# lit-bit.net
KiCad netlist of a schematic drawn in EAGLE
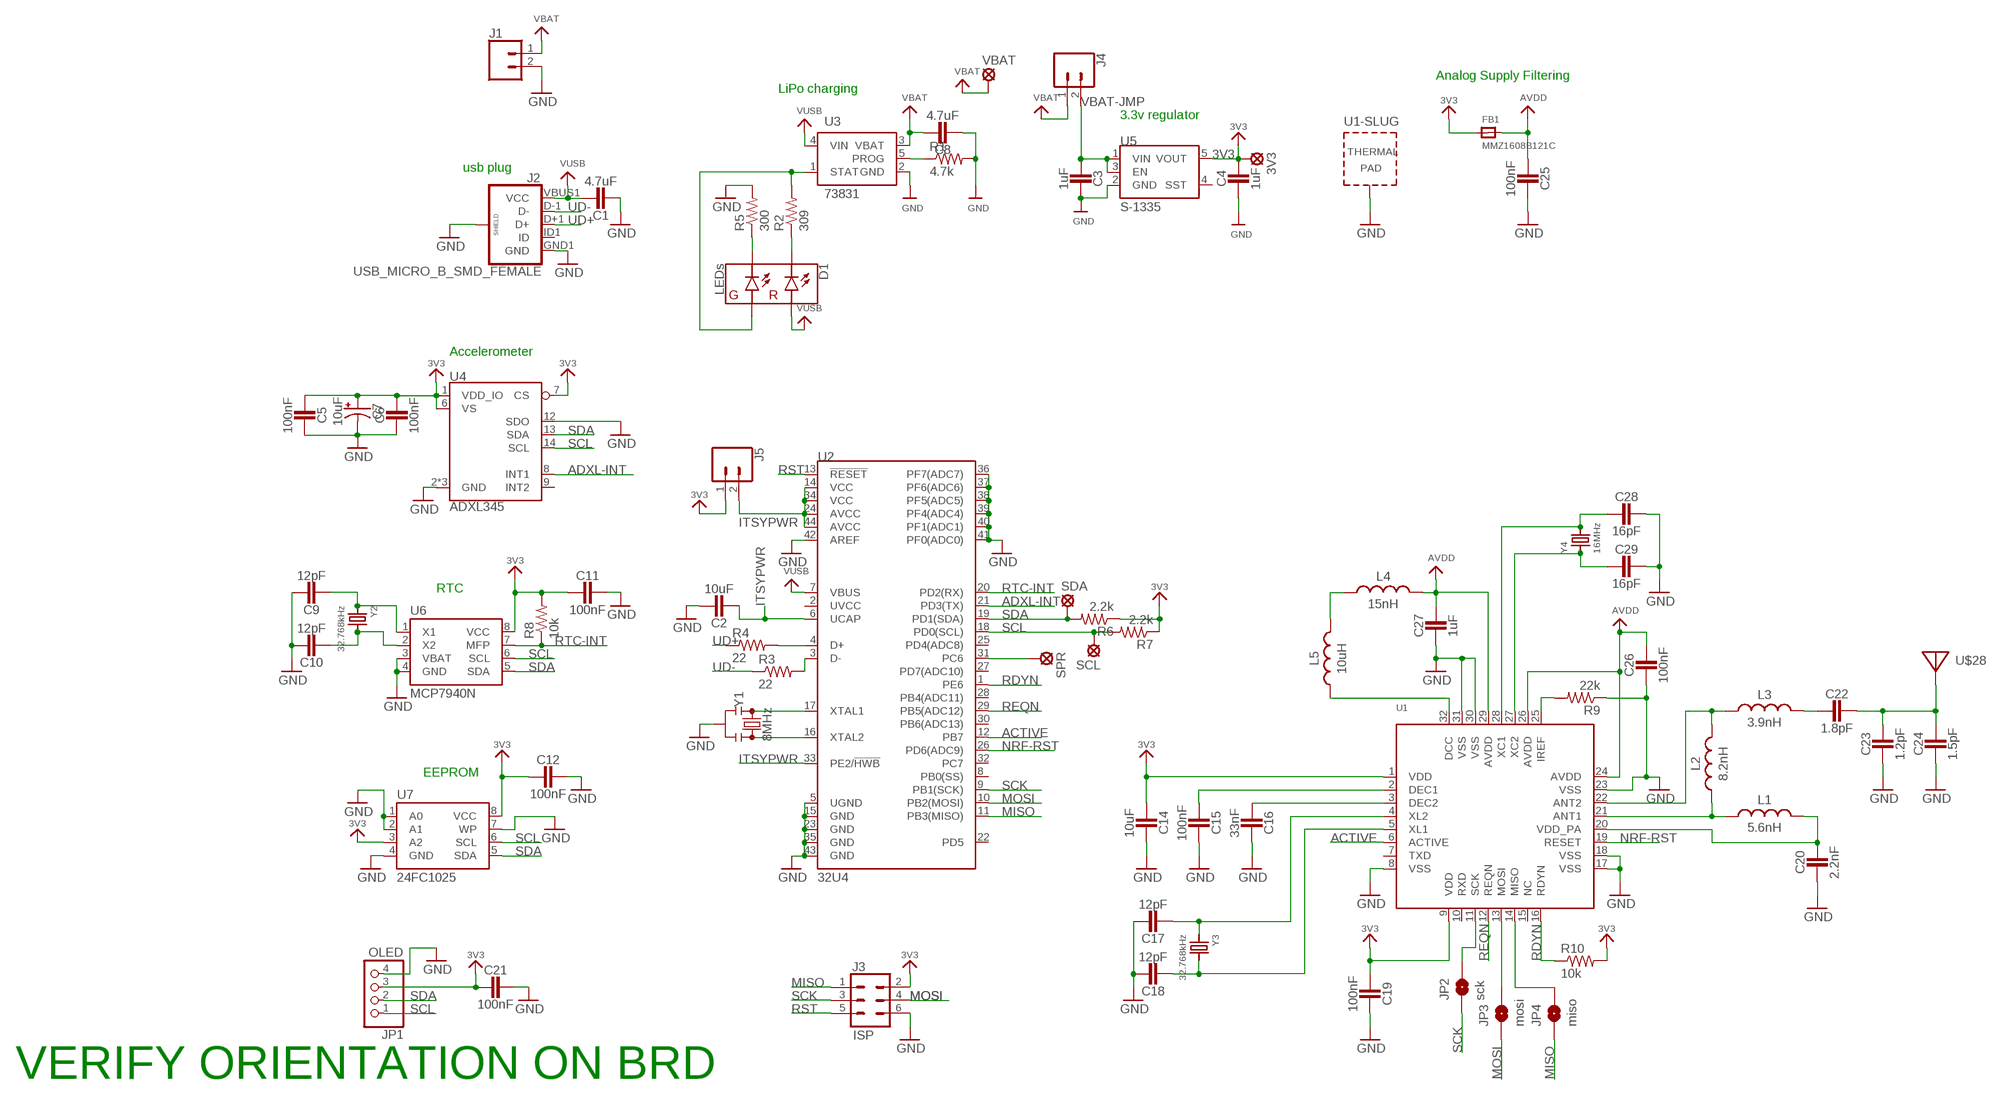
[diagram p0: schematic, sheet 1]

(export (version "E")
  (design (tool "Eeschema 10.0.6"))
  (components
    (comp (ref "3V3")
      (value "LSP10")
      (footprint "eagle-import:LSP10")
      (libsource (lib "eagle-import") (part "LSP10"))
    )
    (comp (ref "C1")
      (value "4.7uF")
      (footprint "eagle-import:0603")
      (libsource (lib "eagle-import") (part "CAP_NONPOL0603"))
    )
    (comp (ref "C2")
      (value "10uF")
      (footprint "eagle-import:0603")
      (libsource (lib "eagle-import") (part "CAP_NONPOL0603"))
    )
    (comp (ref "C3")
      (value "1uF")
      (footprint "eagle-import:0603")
      (libsource (lib "eagle-import") (part "CAP_NONPOL0603"))
    )
    (comp (ref "C4")
      (value "1uF")
      (footprint "eagle-import:0603")
      (libsource (lib "eagle-import") (part "CAP_NONPOL0603"))
    )
    (comp (ref "C5")
      (value "100nF")
      (footprint "eagle-import:0603")
      (libsource (lib "eagle-import") (part "CAP_NONPOL0603"))
    )
    (comp (ref "C6")
      (value "100nF")
      (footprint "eagle-import:0603")
      (libsource (lib "eagle-import") (part "CAP_NONPOL0603"))
    )
    (comp (ref "C7")
      (value "10uF")
      (footprint "eagle-import:0805-POLAR")
      (libsource (lib "eagle-import") (part "CAP_POL"))
    )
    (comp (ref "C8")
      (value "4.7uF")
      (footprint "eagle-import:0603")
      (libsource (lib "eagle-import") (part "CAP_NONPOL0603"))
    )
    (comp (ref "C9")
      (value "12pF")
      (footprint "eagle-import:0603")
      (libsource (lib "eagle-import") (part "CAP_NONPOL0603"))
    )
    (comp (ref "C10")
      (value "12pF")
      (footprint "eagle-import:0603")
      (libsource (lib "eagle-import") (part "CAP_NONPOL0603"))
    )
    (comp (ref "C11")
      (value "100nF")
      (footprint "eagle-import:0603")
      (libsource (lib "eagle-import") (part "CAP_NONPOL0603"))
    )
    (comp (ref "C12")
      (value "100nF")
      (footprint "eagle-import:0603")
      (libsource (lib "eagle-import") (part "CAP_NONPOL0603"))
    )
    (comp (ref "C14")
      (value "10uF")
      (footprint "eagle-import:0603")
      (libsource (lib "eagle-import") (part "CAP_NONPOL0603"))
    )
    (comp (ref "C15")
      (value "100nF")
      (footprint "eagle-import:0603")
      (libsource (lib "eagle-import") (part "CAP_NONPOL0603"))
    )
    (comp (ref "C16")
      (value "33nF")
      (footprint "eagle-import:0603")
      (libsource (lib "eagle-import") (part "CAP_NONPOL0603"))
    )
    (comp (ref "C17")
      (value "12pF")
      (footprint "eagle-import:0603")
      (libsource (lib "eagle-import") (part "CAP_NONPOL0603"))
    )
    (comp (ref "C18")
      (value "12pF")
      (footprint "eagle-import:0603")
      (libsource (lib "eagle-import") (part "CAP_NONPOL0603"))
    )
    (comp (ref "C19")
      (value "100nF")
      (footprint "eagle-import:0603")
      (libsource (lib "eagle-import") (part "CAP_NONPOL0603"))
    )
    (comp (ref "C20")
      (value "2.2nF")
      (footprint "eagle-import:0603")
      (libsource (lib "eagle-import") (part "CAP_NONPOL0603"))
    )
    (comp (ref "C21")
      (value "100nF")
      (footprint "eagle-import:0603")
      (libsource (lib "eagle-import") (part "CAP_NONPOL0603"))
    )
    (comp (ref "C22")
      (value "1.8pF")
      (footprint "eagle-import:0603")
      (libsource (lib "eagle-import") (part "CAP_NONPOL0603"))
    )
    (comp (ref "C23")
      (value "1.2pF")
      (footprint "eagle-import:0603")
      (libsource (lib "eagle-import") (part "CAP_NONPOL0603"))
    )
    (comp (ref "C24")
      (value "1.5pF")
      (footprint "eagle-import:0603")
      (libsource (lib "eagle-import") (part "CAP_NONPOL0603"))
    )
    (comp (ref "C25")
      (value "100nF")
      (footprint "eagle-import:0603")
      (libsource (lib "eagle-import") (part "CAP_NONPOL0603"))
    )
    (comp (ref "C26")
      (value "100nF")
      (footprint "eagle-import:0603")
      (libsource (lib "eagle-import") (part "CAP_NONPOL0603"))
    )
    (comp (ref "C27")
      (value "1uF")
      (footprint "eagle-import:0603")
      (libsource (lib "eagle-import") (part "CAP_NONPOL0603"))
    )
    (comp (ref "C28")
      (value "16pF")
      (footprint "eagle-import:0603")
      (libsource (lib "eagle-import") (part "CAP_NONPOL0603"))
    )
    (comp (ref "C29")
      (value "16pF")
      (footprint "eagle-import:0603")
      (libsource (lib "eagle-import") (part "CAP_NONPOL0603"))
    )
    (comp (ref "D1")
      (value "LEDs")
      (footprint "eagle-import:0606")
      (libsource (lib "eagle-import") (part "LED-RGSMIT"))
    )
    (comp (ref "FB1")
      (value "MMZ1608B121C")
      (footprint "eagle-import:0805")
      (libsource (lib "eagle-import") (part "FERRITE0805"))
    )
    (comp (ref "J1")
      (value "CONN_02-JST-2MM-SMT")
      (footprint "eagle-import:JST-2-SMD")
      (libsource (lib "eagle-import") (part "CONN_02-JST-2MM-SMT"))
    )
    (comp (ref "J2")
      (value "USB_MICRO_B_SMD_FEMALE")
      (footprint "eagle-import:USB-B-MICRO-SMD")
      (libsource (lib "eagle-import") (part "USB_MICRO_B_SMD_FEMALE"))
    )
    (comp (ref "J3")
      (value "ISP")
      (footprint "eagle-import:2X3")
      (libsource (lib "eagle-import") (part "CONN_03X22X3_SILK_MALE_PTH"))
    )
    (comp (ref "J4")
      (value "CONN_02")
      (footprint "eagle-import:1X02")
      (libsource (lib "eagle-import") (part "CONN_02"))
    )
    (comp (ref "J5")
      (value "CONN_02")
      (footprint "eagle-import:1X02")
      (libsource (lib "eagle-import") (part "CONN_02"))
    )
    (comp (ref "JP1")
      (value "OLED")
      (footprint "eagle-import:1X04_ROUND")
      (libsource (lib "eagle-import") (part "HEADER-1X4ROUND"))
    )
    (comp (ref "JP2")
      (value "sck")
      (footprint "eagle-import:SMT-JUMPER_2_NO_SILK")
      (libsource (lib "eagle-import") (part "JUMPER-SMT_2_NO_SILK"))
    )
    (comp (ref "JP3")
      (value "mosi")
      (footprint "eagle-import:SMT-JUMPER_2_NO_SILK")
      (libsource (lib "eagle-import") (part "JUMPER-SMT_2_NO_SILK"))
    )
    (comp (ref "JP4")
      (value "miso")
      (footprint "eagle-import:SMT-JUMPER_2_NO_SILK")
      (libsource (lib "eagle-import") (part "JUMPER-SMT_2_NO_SILK"))
    )
    (comp (ref "L1")
      (value "5.6nH")
      (footprint "eagle-import:0603")
      (libsource (lib "eagle-import") (part "INDUCTOR0603"))
    )
    (comp (ref "L2")
      (value "8.2nH")
      (footprint "eagle-import:0603")
      (libsource (lib "eagle-import") (part "INDUCTOR0603"))
    )
    (comp (ref "L3")
      (value "3.9nH")
      (footprint "eagle-import:0603")
      (libsource (lib "eagle-import") (part "INDUCTOR0603"))
    )
    (comp (ref "L4")
      (value "15nH")
      (footprint "eagle-import:0603")
      (libsource (lib "eagle-import") (part "INDUCTOR0603"))
    )
    (comp (ref "L5")
      (value "10uH")
      (footprint "eagle-import:0603")
      (libsource (lib "eagle-import") (part "INDUCTOR0603"))
    )
    (comp (ref "R1")
      (value "4.7k")
      (footprint "eagle-import:0603")
      (libsource (lib "eagle-import") (part "RES-0603"))
    )
    (comp (ref "R2")
      (value "309")
      (footprint "eagle-import:0603")
      (libsource (lib "eagle-import") (part "RES-0603"))
    )
    (comp (ref "R3")
      (value "22")
      (footprint "eagle-import:0603")
      (libsource (lib "eagle-import") (part "RES-0603"))
    )
    (comp (ref "R4")
      (value "22")
      (footprint "eagle-import:0603")
      (libsource (lib "eagle-import") (part "RES-0603"))
    )
    (comp (ref "R5")
      (value "300")
      (footprint "eagle-import:0603")
      (libsource (lib "eagle-import") (part "RES-0603"))
    )
    (comp (ref "R6")
      (value "2.2k")
      (footprint "eagle-import:0603")
      (libsource (lib "eagle-import") (part "RES-0603"))
    )
    (comp (ref "R7")
      (value "2.2k")
      (footprint "eagle-import:0603")
      (libsource (lib "eagle-import") (part "RES-0603"))
    )
    (comp (ref "R8")
      (value "10k")
      (footprint "eagle-import:0603")
      (libsource (lib "eagle-import") (part "RES-0603"))
    )
    (comp (ref "R9")
      (value "22k")
      (footprint "eagle-import:0603")
      (libsource (lib "eagle-import") (part "RES-0603"))
    )
    (comp (ref "R10")
      (value "10k")
      (footprint "eagle-import:0603")
      (libsource (lib "eagle-import") (part "RES-0603"))
    )
    (comp (ref "SCL")
      (value "LSP10")
      (footprint "eagle-import:LSP10")
      (libsource (lib "eagle-import") (part "LSP10"))
    )
    (comp (ref "SDA")
      (value "LSP10")
      (footprint "eagle-import:LSP10")
      (libsource (lib "eagle-import") (part "LSP10"))
    )
    (comp (ref "SPR")
      (value "LSP10")
      (footprint "eagle-import:LSP10")
      (libsource (lib "eagle-import") (part "LSP10"))
    )
    (comp (ref "U$28")
      (value "ANTENNA_PCBNRF8001_1.6MM")
      (footprint "eagle-import:ANT_PCB_2.4GHZ_NRF8001_1.6MM_1OZ")
      (libsource (lib "eagle-import") (part "ANTENNA_PCBNRF8001_1.6MM"))
    )
    (comp (ref "U1")
      (value "NRF8001")
      (footprint "eagle-import:QFN32_5MM")
      (libsource (lib "eagle-import") (part "NRF8001"))
    )
    (comp (ref "U2")
      (value "32U4")
      (footprint "eagle-import:TQFP44")
      (libsource (lib "eagle-import") (part "ATMEGA32U4TQFP-44"))
    )
    (comp (ref "U3")
      (value "73831")
      (footprint "eagle-import:SOT23-5")
      (libsource (lib "eagle-import") (part "MCP73831T"))
    )
    (comp (ref "U4")
      (value "ADXL345")
      (footprint "eagle-import:LGA-14")
      (libsource (lib "eagle-import") (part "ADXL345"))
    )
    (comp (ref "U5")
      (value "S-1335")
      (footprint "eagle-import:SOT23-5")
      (libsource (lib "eagle-import") (part "S-1335M33"))
    )
    (comp (ref "U6")
      (value "MCP7940N")
      (footprint "eagle-import:8-SOIC_HAND_SOLDER")
      (libsource (lib "eagle-import") (part "MCP7940N"))
    )
    (comp (ref "U7")
      (value "24FC1025")
      (footprint "eagle-import:8-SOIC_HAND_SOLDER")
      (libsource (lib "eagle-import") (part "24FC1025"))
    )
    (comp (ref "VBAT")
      (value "LSP10")
      (footprint "eagle-import:LSP10")
      (libsource (lib "eagle-import") (part "LSP10"))
    )
    (comp (ref "Y1")
      (value "8MHz")
      (footprint "eagle-import:RESONATOR-SMD-3.2X1.3")
      (libsource (lib "eagle-import") (part "RESONATOR-8MHZSMD_3.2X1.3"))
    )
    (comp (ref "Y2")
      (value "32.768kHz")
      (footprint "eagle-import:CRYSTAL_8X3.8")
      (libsource (lib "eagle-import") (part "CRYSTAL8X3.8SMT"))
    )
    (comp (ref "Y3")
      (value "32.768kHz")
      (footprint "eagle-import:CRYSTAL_8X3.8")
      (libsource (lib "eagle-import") (part "CRYSTAL8X3.8SMT"))
    )
    (comp (ref "Y4")
      (value "16MHz")
      (footprint "eagle-import:CRYSTAL_3.2X2.5")
      (libsource (lib "eagle-import") (part "CRYSTALTHIN"))
    )
  )
  (nets
    (net (code "1") (name "/ACTIVE") (class "Default")
      (node (ref "U1") (pin "6") (pinfunction "ACTIVE_6") (pintype "output"))
      (node (ref "U2") (pin "12") (pinfunction "PB7_12") (pintype "bidirectional"))
    )
    (net (code "2") (name "/ADXL-INT") (class "Default")
      (node (ref "U2") (pin "21") (pinfunction "PD3(TX)_21") (pintype "bidirectional"))
      (node (ref "U4") (pin "8") (pinfunction "INT1_8") (pintype "output"))
    )
    (net (code "3") (name "/ITSYPWR") (class "Default")
      (node (ref "C2") (pin "2") (pinfunction "2_2") (pintype "passive"))
      (node (ref "J5") (pin "2") (pinfunction "2_2") (pintype "passive"))
      (node (ref "U2") (pin "14") (pinfunction "VCC_14") (pintype "bidirectional"))
      (node (ref "U2") (pin "24") (pinfunction "AVCC_24") (pintype "bidirectional"))
      (node (ref "U2") (pin "33") (pinfunction "PE2/~{HWB}_33") (pintype "bidirectional"))
      (node (ref "U2") (pin "34") (pinfunction "VCC_34") (pintype "bidirectional"))
      (node (ref "U2") (pin "44") (pinfunction "AVCC_44") (pintype "bidirectional"))
      (node (ref "U2") (pin "6") (pinfunction "UCAP_6") (pintype "bidirectional"))
    )
    (net (code "4") (name "/MISO") (class "Default")
      (node (ref "J3") (pin "1") (pinfunction "1_1") (pintype "bidirectional"))
      (node (ref "JP4") (pin "1") (pinfunction "1_1") (pintype "passive"))
      (node (ref "U2") (pin "11") (pinfunction "PB3(MISO)_11") (pintype "bidirectional"))
    )
    (net (code "5") (name "/MOSI") (class "Default")
      (node (ref "J3") (pin "4") (pinfunction "4_4") (pintype "bidirectional"))
      (node (ref "JP3") (pin "1") (pinfunction "1_1") (pintype "passive"))
      (node (ref "U2") (pin "10") (pinfunction "PB2(MOSI)_10") (pintype "bidirectional"))
    )
    (net (code "6") (name "/NRF-RST") (class "Default")
      (node (ref "U1") (pin "19") (pinfunction "RESET_19") (pintype "input"))
      (node (ref "U2") (pin "26") (pinfunction "PD6(ADC9)_26") (pintype "bidirectional"))
    )
    (net (code "7") (name "/RDYN") (class "Default")
      (node (ref "R10") (pin "1") (pinfunction "1_1") (pintype "passive"))
      (node (ref "U1") (pin "16") (pinfunction "RDYN_16") (pintype "output"))
      (node (ref "U2") (pin "1") (pinfunction "PE6_1") (pintype "bidirectional"))
    )
    (net (code "8") (name "/REQN") (class "Default")
      (node (ref "U1") (pin "12") (pinfunction "REQN_12") (pintype "input"))
      (node (ref "U2") (pin "29") (pinfunction "PB5(ADC12)_29") (pintype "bidirectional"))
    )
    (net (code "9") (name "/RST") (class "Default")
      (node (ref "J3") (pin "5") (pinfunction "5_5") (pintype "bidirectional"))
      (node (ref "U2") (pin "13") (pinfunction "~{RESET}_13") (pintype "bidirectional"))
    )
    (net (code "10") (name "/RTC-INT") (class "Default")
      (node (ref "R8") (pin "1") (pinfunction "1_1") (pintype "passive"))
      (node (ref "U2") (pin "20") (pinfunction "PD2(RX)_20") (pintype "bidirectional"))
      (node (ref "U6") (pin "7") (pinfunction "MFP_7") (pintype "output"))
    )
    (net (code "11") (name "/SCK") (class "Default")
      (node (ref "J3") (pin "3") (pinfunction "3_3") (pintype "bidirectional"))
      (node (ref "JP2") (pin "1") (pinfunction "1_1") (pintype "passive"))
      (node (ref "U2") (pin "9") (pinfunction "PB1(SCK)_9") (pintype "bidirectional"))
    )
    (net (code "12") (name "/SCL") (class "Default")
      (node (ref "JP1") (pin "1") (pinfunction "1_1") (pintype "passive"))
      (node (ref "R7") (pin "2") (pinfunction "2_2") (pintype "passive"))
      (node (ref "SCL") (pin "MP") (pinfunction "MP_MP") (pintype "passive"))
      (node (ref "U2") (pin "18") (pinfunction "PD0(SCL)_18") (pintype "bidirectional"))
      (node (ref "U4") (pin "14") (pinfunction "SCL_14") (pintype "bidirectional"))
      (node (ref "U6") (pin "6") (pinfunction "SCL_6") (pintype "bidirectional"))
      (node (ref "U7") (pin "6") (pinfunction "SCL_6") (pintype "bidirectional"))
    )
    (net (code "13") (name "/SDA") (class "Default")
      (node (ref "JP1") (pin "2") (pinfunction "2_2") (pintype "passive"))
      (node (ref "R6") (pin "2") (pinfunction "2_2") (pintype "passive"))
      (node (ref "SDA") (pin "MP") (pinfunction "MP_MP") (pintype "passive"))
      (node (ref "U2") (pin "19") (pinfunction "PD1(SDA)_19") (pintype "bidirectional"))
      (node (ref "U4") (pin "13") (pinfunction "SDA_13") (pintype "bidirectional"))
      (node (ref "U6") (pin "5") (pinfunction "SDA_5") (pintype "bidirectional"))
      (node (ref "U7") (pin "5") (pinfunction "SDA_5") (pintype "bidirectional"))
    )
    (net (code "14") (name "/UD+") (class "Default")
      (node (ref "J2") (pin "D+1") (pinfunction "D+_D+1") (pintype "bidirectional"))
      (node (ref "R4") (pin "1") (pinfunction "1_1") (pintype "passive"))
    )
    (net (code "15") (name "/UD-") (class "Default")
      (node (ref "J2") (pin "D-1") (pinfunction "D-_D-1") (pintype "bidirectional"))
      (node (ref "R3") (pin "1") (pinfunction "1_1") (pintype "passive"))
    )
    (net (code "16") (name "/VBAT-JMP") (class "Default")
      (node (ref "C3") (pin "2") (pinfunction "2_2") (pintype "passive"))
      (node (ref "J4") (pin "2") (pinfunction "2_2") (pintype "passive"))
      (node (ref "U5") (pin "1") (pinfunction "VIN_1") (pintype "passive"))
      (node (ref "U5") (pin "3") (pinfunction "EN_3") (pintype "bidirectional"))
    )
    (net (code "17") (name "3V3") (class "Default")
      (node (ref "3V3") (pin "MP") (pinfunction "MP_MP") (pintype "passive"))
      (node (ref "C11") (pin "2") (pinfunction "2_2") (pintype "passive"))
      (node (ref "C12") (pin "2") (pinfunction "2_2") (pintype "passive"))
      (node (ref "C14") (pin "2") (pinfunction "2_2") (pintype "passive"))
      (node (ref "C19") (pin "2") (pinfunction "2_2") (pintype "passive"))
      (node (ref "C21") (pin "2") (pinfunction "2_2") (pintype "passive"))
      (node (ref "C4") (pin "1") (pinfunction "1_1") (pintype "passive"))
      (node (ref "C5") (pin "2") (pinfunction "2_2") (pintype "passive"))
      (node (ref "C6") (pin "1") (pinfunction "1_1") (pintype "passive"))
      (node (ref "C7") (pin "1") (pinfunction "+_1") (pintype "passive"))
      (node (ref "FB1") (pin "1") (pinfunction "P$1_1") (pintype "passive"))
      (node (ref "J3") (pin "2") (pinfunction "2_2") (pintype "bidirectional"))
      (node (ref "J5") (pin "1") (pinfunction "1_1") (pintype "passive"))
      (node (ref "JP1") (pin "3") (pinfunction "3_3") (pintype "passive"))
      (node (ref "R10") (pin "2") (pinfunction "2_2") (pintype "passive"))
      (node (ref "R6") (pin "1") (pinfunction "1_1") (pintype "passive"))
      (node (ref "R7") (pin "1") (pinfunction "1_1") (pintype "passive"))
      (node (ref "R8") (pin "2") (pinfunction "2_2") (pintype "passive"))
      (node (ref "U1") (pin "1") (pinfunction "VDD_1") (pintype "power_in"))
      (node (ref "U1") (pin "9") (pinfunction "VDD_9") (pintype "power_in"))
      (node (ref "U4") (pin "1") (pinfunction "VDD_IO_1") (pintype "passive"))
      (node (ref "U4") (pin "6") (pinfunction "VS_6") (pintype "passive"))
      (node (ref "U4") (pin "7") (pinfunction "CS_7") (pintype "bidirectional"))
      (node (ref "U5") (pin "5") (pinfunction "VOUT_5") (pintype "passive"))
      (node (ref "U6") (pin "8") (pinfunction "VCC_8") (pintype "passive"))
      (node (ref "U7") (pin "3") (pinfunction "A2_3") (pintype "bidirectional"))
      (node (ref "U7") (pin "8") (pinfunction "VCC_8") (pintype "power_in"))
    )
    (net (code "18") (name "AVDD") (class "Default")
      (node (ref "C25") (pin "2") (pinfunction "2_2") (pintype "passive"))
      (node (ref "C26") (pin "1") (pinfunction "1_1") (pintype "passive"))
      (node (ref "C27") (pin "1") (pinfunction "1_1") (pintype "passive"))
      (node (ref "FB1") (pin "2") (pinfunction "P$2_2") (pintype "passive"))
      (node (ref "L4") (pin "2") (pinfunction "2_2") (pintype "passive"))
      (node (ref "U1") (pin "24") (pinfunction "AVDD_24") (pintype "power_in"))
      (node (ref "U1") (pin "26") (pinfunction "AVDD_26") (pintype "power_in"))
      (node (ref "U1") (pin "29") (pinfunction "AVDD_29") (pintype "power_in"))
    )
    (net (code "19") (name "GND") (class "Default")
      (node (ref "C1") (pin "2") (pinfunction "2_2") (pintype "passive"))
      (node (ref "C10") (pin "1") (pinfunction "1_1") (pintype "passive"))
      (node (ref "C11") (pin "1") (pinfunction "1_1") (pintype "passive"))
      (node (ref "C12") (pin "1") (pinfunction "1_1") (pintype "passive"))
      (node (ref "C14") (pin "1") (pinfunction "1_1") (pintype "passive"))
      (node (ref "C15") (pin "1") (pinfunction "1_1") (pintype "passive"))
      (node (ref "C16") (pin "1") (pinfunction "1_1") (pintype "passive"))
      (node (ref "C17") (pin "1") (pinfunction "1_1") (pintype "passive"))
      (node (ref "C18") (pin "1") (pinfunction "1_1") (pintype "passive"))
      (node (ref "C19") (pin "1") (pinfunction "1_1") (pintype "passive"))
      (node (ref "C2") (pin "1") (pinfunction "1_1") (pintype "passive"))
      (node (ref "C20") (pin "2") (pinfunction "2_2") (pintype "passive"))
      (node (ref "C21") (pin "1") (pinfunction "1_1") (pintype "passive"))
      (node (ref "C23") (pin "2") (pinfunction "2_2") (pintype "passive"))
      (node (ref "C24") (pin "2") (pinfunction "2_2") (pintype "passive"))
      (node (ref "C25") (pin "1") (pinfunction "1_1") (pintype "passive"))
      (node (ref "C26") (pin "2") (pinfunction "2_2") (pintype "passive"))
      (node (ref "C27") (pin "2") (pinfunction "2_2") (pintype "passive"))
      (node (ref "C28") (pin "1") (pinfunction "1_1") (pintype "passive"))
      (node (ref "C29") (pin "1") (pinfunction "1_1") (pintype "passive"))
      (node (ref "C3") (pin "1") (pinfunction "1_1") (pintype "passive"))
      (node (ref "C4") (pin "2") (pinfunction "2_2") (pintype "passive"))
      (node (ref "C5") (pin "1") (pinfunction "1_1") (pintype "passive"))
      (node (ref "C6") (pin "2") (pinfunction "2_2") (pintype "passive"))
      (node (ref "C7") (pin "2") (pinfunction "-_2") (pintype "passive"))
      (node (ref "C8") (pin "2") (pinfunction "2_2") (pintype "passive"))
      (node (ref "C9") (pin "1") (pinfunction "1_1") (pintype "passive"))
      (node (ref "J1") (pin "2") (pinfunction "1_2") (pintype "passive"))
      (node (ref "J2") (pin "GND1") (pinfunction "GND_GND1") (pintype "passive"))
      (node (ref "J2") (pin "P$1") (pinfunction "SHIELD_P$1") (pintype "passive"))
      (node (ref "J2") (pin "P$3") (pinfunction "SHIELD_P$3") (pintype "passive"))
      (node (ref "J2") (pin "P$4") (pinfunction "SHIELD_P$4") (pintype "passive"))
      (node (ref "J2") (pin "P$5") (pinfunction "SHIELD_P$5") (pintype "passive"))
      (node (ref "J3") (pin "6") (pinfunction "6_6") (pintype "bidirectional"))
      (node (ref "JP1") (pin "4") (pinfunction "4_4") (pintype "passive"))
      (node (ref "R1") (pin "2") (pinfunction "2_2") (pintype "passive"))
      (node (ref "R5") (pin "2") (pinfunction "2_2") (pintype "passive"))
      (node (ref "R9") (pin "1") (pinfunction "1_1") (pintype "passive"))
      (node (ref "U1") (pin "17") (pinfunction "VSS_17") (pintype "power_in"))
      (node (ref "U1") (pin "18") (pinfunction "VSS_18") (pintype "power_in"))
      (node (ref "U1") (pin "23") (pinfunction "VSS_23") (pintype "power_in"))
      (node (ref "U1") (pin "30") (pinfunction "VSS_30") (pintype "power_in"))
      (node (ref "U1") (pin "31") (pinfunction "VSS_31") (pintype "power_in"))
      (node (ref "U1") (pin "33") (pinfunction "TP_33") (pintype "power_in"))
      (node (ref "U1") (pin "8") (pinfunction "VSS_8") (pintype "power_in"))
      (node (ref "U2") (pin "15") (pinfunction "GND_15") (pintype "bidirectional"))
      (node (ref "U2") (pin "23") (pinfunction "GND_23") (pintype "bidirectional"))
      (node (ref "U2") (pin "35") (pinfunction "GND_35") (pintype "bidirectional"))
      (node (ref "U2") (pin "36") (pinfunction "PF7(ADC7)_36") (pintype "bidirectional"))
      (node (ref "U2") (pin "37") (pinfunction "PF6(ADC6)_37") (pintype "bidirectional"))
      (node (ref "U2") (pin "38") (pinfunction "PF5(ADC5)_38") (pintype "bidirectional"))
      (node (ref "U2") (pin "39") (pinfunction "PF4(ADC4)_39") (pintype "bidirectional"))
      (node (ref "U2") (pin "40") (pinfunction "PF1(ADC1)_40") (pintype "bidirectional"))
      (node (ref "U2") (pin "41") (pinfunction "PF0(ADC0)_41") (pintype "bidirectional"))
      (node (ref "U2") (pin "42") (pinfunction "AREF_42") (pintype "bidirectional"))
      (node (ref "U2") (pin "43") (pinfunction "GND_43") (pintype "bidirectional"))
      (node (ref "U2") (pin "5") (pinfunction "UGND_5") (pintype "bidirectional"))
      (node (ref "U3") (pin "2") (pinfunction "GND_2") (pintype "passive"))
      (node (ref "U4") (pin "12") (pinfunction "SDO_12") (pintype "bidirectional"))
      (node (ref "U4") (pin "2") (pinfunction "GND_2") (pintype "passive"))
      (node (ref "U4") (pin "4") (pinfunction "GND_4") (pintype "passive"))
      (node (ref "U4") (pin "5") (pinfunction "GND_5") (pintype "passive"))
      (node (ref "U5") (pin "2") (pinfunction "GND_2") (pintype "passive"))
      (node (ref "U6") (pin "3") (pinfunction "VBAT_3") (pintype "passive"))
      (node (ref "U6") (pin "4") (pinfunction "GND_4") (pintype "passive"))
      (node (ref "U7") (pin "1") (pinfunction "A0_1") (pintype "bidirectional"))
      (node (ref "U7") (pin "2") (pinfunction "A1_2") (pintype "bidirectional"))
      (node (ref "U7") (pin "4") (pinfunction "GND_4") (pintype "power_in"))
      (node (ref "U7") (pin "7") (pinfunction "WP_7") (pintype "bidirectional"))
      (node (ref "Y1") (pin "2") (pinfunction "2_2") (pintype "passive"))
    )
    (net (code "20") (name "Net-(C22-Pad2)") (class "Default")
      (node (ref "C22") (pin "2") (pinfunction "2_2") (pintype "passive"))
      (node (ref "L3") (pin "2") (pinfunction "2_2") (pintype "passive"))
    )
    (net (code "21") (name "Net-(D1-GA)") (class "Default")
      (node (ref "D1") (pin "P$3") (pinfunction "GA_P$3") (pintype "passive"))
      (node (ref "R2") (pin "2") (pinfunction "2_2") (pintype "passive"))
      (node (ref "U3") (pin "1") (pinfunction "STAT_1") (pintype "bidirectional"))
    )
    (net (code "22") (name "Net-(D1-GC)") (class "Default")
      (node (ref "D1") (pin "P$4") (pinfunction "GC_P$4") (pintype "passive"))
      (node (ref "R5") (pin "1") (pinfunction "1_1") (pintype "passive"))
    )
    (net (code "23") (name "Net-(D1-RC)") (class "Default")
      (node (ref "D1") (pin "P$2") (pinfunction "RC_P$2") (pintype "passive"))
      (node (ref "R2") (pin "1") (pinfunction "1_1") (pintype "passive"))
    )
    (net (code "24") (name "Net-(L4-Pad1)") (class "Default")
      (node (ref "L4") (pin "1") (pinfunction "1_1") (pintype "passive"))
      (node (ref "L5") (pin "2") (pinfunction "2_2") (pintype "passive"))
    )
    (net (code "25") (name "Net-(U$28-P$1)") (class "Default")
      (node (ref "C22") (pin "1") (pinfunction "1_1") (pintype "passive"))
      (node (ref "C23") (pin "1") (pinfunction "1_1") (pintype "passive"))
      (node (ref "C24") (pin "1") (pinfunction "1_1") (pintype "passive"))
      (node (ref "U$28") (pin "FEED") (pinfunction "P$1_FEED") (pintype "passive"))
    )
    (net (code "26") (name "Net-(U1B-ANT1)") (class "Default")
      (node (ref "L1") (pin "1") (pinfunction "1_1") (pintype "passive"))
      (node (ref "L2") (pin "1") (pinfunction "1_1") (pintype "passive"))
      (node (ref "U1") (pin "21") (pinfunction "ANT1_21") (pintype "bidirectional"))
    )
    (net (code "27") (name "Net-(U1B-ANT2)") (class "Default")
      (node (ref "L2") (pin "2") (pinfunction "2_2") (pintype "passive"))
      (node (ref "L3") (pin "1") (pinfunction "1_1") (pintype "passive"))
      (node (ref "U1") (pin "22") (pinfunction "ANT2_22") (pintype "bidirectional"))
    )
    (net (code "28") (name "Net-(U1B-DCC)") (class "Default")
      (node (ref "L5") (pin "1") (pinfunction "1_1") (pintype "passive"))
      (node (ref "U1") (pin "32") (pinfunction "DCC_32") (pintype "bidirectional"))
    )
    (net (code "29") (name "Net-(U1B-DEC1)") (class "Default")
      (node (ref "C15") (pin "2") (pinfunction "2_2") (pintype "passive"))
      (node (ref "U1") (pin "2") (pinfunction "DEC1_2") (pintype "bidirectional"))
    )
    (net (code "30") (name "Net-(U1B-DEC2)") (class "Default")
      (node (ref "C16") (pin "2") (pinfunction "2_2") (pintype "passive"))
      (node (ref "U1") (pin "3") (pinfunction "DEC2_3") (pintype "bidirectional"))
    )
    (net (code "31") (name "Net-(U1B-IREF)") (class "Default")
      (node (ref "R9") (pin "2") (pinfunction "2_2") (pintype "passive"))
      (node (ref "U1") (pin "25") (pinfunction "IREF_25") (pintype "output"))
    )
    (net (code "32") (name "Net-(U1B-MISO)") (class "Default")
      (node (ref "JP4") (pin "2") (pinfunction "2_2") (pintype "passive"))
      (node (ref "U1") (pin "14") (pinfunction "MISO_14") (pintype "output"))
    )
    (net (code "33") (name "Net-(U1B-MOSI)") (class "Default")
      (node (ref "JP3") (pin "2") (pinfunction "2_2") (pintype "passive"))
      (node (ref "U1") (pin "13") (pinfunction "MOSI_13") (pintype "input"))
    )
    (net (code "34") (name "Net-(U1B-SCK)") (class "Default")
      (node (ref "JP2") (pin "2") (pinfunction "2_2") (pintype "passive"))
      (node (ref "U1") (pin "11") (pinfunction "SCK_11") (pintype "input"))
    )
    (net (code "35") (name "Net-(U1B-VDD_PA)") (class "Default")
      (node (ref "C20") (pin "1") (pinfunction "1_1") (pintype "passive"))
      (node (ref "L1") (pin "2") (pinfunction "2_2") (pintype "passive"))
      (node (ref "U1") (pin "20") (pinfunction "VDD_PA_20") (pintype "bidirectional"))
    )
    (net (code "36") (name "Net-(U1B-XC1)") (class "Default")
      (node (ref "C28") (pin "2") (pinfunction "2_2") (pintype "passive"))
      (node (ref "U1") (pin "28") (pinfunction "XC1_28") (pintype "input"))
      (node (ref "Y4") (pin "2") (pinfunction "2_2") (pintype "passive"))
    )
    (net (code "37") (name "Net-(U1B-XC2)") (class "Default")
      (node (ref "C29") (pin "2") (pinfunction "2_2") (pintype "passive"))
      (node (ref "U1") (pin "27") (pinfunction "XC2_27") (pintype "output"))
      (node (ref "Y4") (pin "1") (pinfunction "1_1") (pintype "passive"))
    )
    (net (code "38") (name "Net-(U1B-XL1)") (class "Default")
      (node (ref "C18") (pin "2") (pinfunction "2_2") (pintype "passive"))
      (node (ref "U1") (pin "5") (pinfunction "XL1_5") (pintype "input"))
      (node (ref "Y3") (pin "P$4") (pinfunction "2_P$4") (pintype "passive"))
    )
    (net (code "39") (name "Net-(U1B-XL2)") (class "Default")
      (node (ref "C17") (pin "2") (pinfunction "2_2") (pintype "passive"))
      (node (ref "U1") (pin "4") (pinfunction "XL2_4") (pintype "output"))
      (node (ref "Y3") (pin "P$1") (pinfunction "1_P$1") (pintype "passive"))
    )
    (net (code "40") (name "Net-(U2-D+)") (class "Default")
      (node (ref "R4") (pin "2") (pinfunction "2_2") (pintype "passive"))
      (node (ref "U2") (pin "4") (pinfunction "D+_4") (pintype "bidirectional"))
    )
    (net (code "41") (name "Net-(U2-D-)") (class "Default")
      (node (ref "R3") (pin "2") (pinfunction "2_2") (pintype "passive"))
      (node (ref "U2") (pin "3") (pinfunction "D-_3") (pintype "bidirectional"))
    )
    (net (code "42") (name "Net-(U2-PC6)") (class "Default")
      (node (ref "SPR") (pin "MP") (pinfunction "MP_MP") (pintype "passive"))
      (node (ref "U2") (pin "31") (pinfunction "PC6_31") (pintype "bidirectional"))
    )
    (net (code "43") (name "Net-(U2-XTAL1)") (class "Default")
      (node (ref "U2") (pin "17") (pinfunction "XTAL1_17") (pintype "bidirectional"))
      (node (ref "Y1") (pin "1") (pinfunction "1_1") (pintype "passive"))
    )
    (net (code "44") (name "Net-(U2-XTAL2)") (class "Default")
      (node (ref "U2") (pin "16") (pinfunction "XTAL2_16") (pintype "bidirectional"))
      (node (ref "Y1") (pin "3") (pinfunction "3_3") (pintype "passive"))
    )
    (net (code "45") (name "Net-(U3-PROG)") (class "Default")
      (node (ref "R1") (pin "1") (pinfunction "1_1") (pintype "passive"))
      (node (ref "U3") (pin "5") (pinfunction "PROG_5") (pintype "bidirectional"))
    )
    (net (code "46") (name "Net-(U6-X1)") (class "Default")
      (node (ref "C9") (pin "2") (pinfunction "2_2") (pintype "passive"))
      (node (ref "U6") (pin "1") (pinfunction "X1_1") (pintype "bidirectional"))
      (node (ref "Y2") (pin "P$1") (pinfunction "1_P$1") (pintype "passive"))
    )
    (net (code "47") (name "Net-(U6-X2)") (class "Default")
      (node (ref "C10") (pin "2") (pinfunction "2_2") (pintype "passive"))
      (node (ref "U6") (pin "2") (pinfunction "X2_2") (pintype "bidirectional"))
      (node (ref "Y2") (pin "P$4") (pinfunction "2_P$4") (pintype "passive"))
    )
    (net (code "48") (name "VBAT") (class "Default")
      (node (ref "C8") (pin "1") (pinfunction "1_1") (pintype "passive"))
      (node (ref "J1") (pin "1") (pinfunction "2_1") (pintype "passive"))
      (node (ref "J4") (pin "1") (pinfunction "1_1") (pintype "passive"))
      (node (ref "U3") (pin "3") (pinfunction "VBAT_3") (pintype "passive"))
      (node (ref "VBAT") (pin "MP") (pinfunction "MP_MP") (pintype "passive"))
    )
    (net (code "49") (name "VUSB") (class "Default")
      (node (ref "C1") (pin "1") (pinfunction "1_1") (pintype "passive"))
      (node (ref "D1") (pin "P$1") (pinfunction "RA_P$1") (pintype "passive"))
      (node (ref "J2") (pin "VBUS1") (pinfunction "VCC_VBUS1") (pintype "passive"))
      (node (ref "U2") (pin "7") (pinfunction "VBUS_7") (pintype "bidirectional"))
      (node (ref "U3") (pin "4") (pinfunction "VIN_4") (pintype "bidirectional"))
    )
    (net (code "50") (name "unconnected-(J2-ID-PadID1)") (class "Default")
      (node (ref "J2") (pin "ID1") (pinfunction "ID_ID1") (pintype "bidirectional"))
    )
    (net (code "51") (name "unconnected-(U1B-NC-Pad15)") (class "Default")
      (node (ref "U1") (pin "15") (pinfunction "NC_15") (pintype "no_connect"))
    )
    (net (code "52") (name "unconnected-(U1B-RXD-Pad10)") (class "Default")
      (node (ref "U1") (pin "10") (pinfunction "RXD_10") (pintype "input"))
    )
    (net (code "53") (name "unconnected-(U1B-TXD-Pad7)") (class "Default")
      (node (ref "U1") (pin "7") (pinfunction "TXD_7") (pintype "output"))
    )
    (net (code "54") (name "unconnected-(U2-PB0(SS)-Pad8)") (class "Default")
      (node (ref "U2") (pin "8") (pinfunction "PB0(SS)_8") (pintype "bidirectional"))
    )
    (net (code "55") (name "unconnected-(U2-PB4(ADC11)-Pad28)") (class "Default")
      (node (ref "U2") (pin "28") (pinfunction "PB4(ADC11)_28") (pintype "bidirectional"))
    )
    (net (code "56") (name "unconnected-(U2-PB6(ADC13)-Pad30)") (class "Default")
      (node (ref "U2") (pin "30") (pinfunction "PB6(ADC13)_30") (pintype "bidirectional"))
    )
    (net (code "57") (name "unconnected-(U2-PC7-Pad32)") (class "Default")
      (node (ref "U2") (pin "32") (pinfunction "PC7_32") (pintype "bidirectional"))
    )
    (net (code "58") (name "unconnected-(U2-PD4(ADC8)-Pad25)") (class "Default")
      (node (ref "U2") (pin "25") (pinfunction "PD4(ADC8)_25") (pintype "bidirectional"))
    )
    (net (code "59") (name "unconnected-(U2-PD5-Pad22)") (class "Default")
      (node (ref "U2") (pin "22") (pinfunction "PD5_22") (pintype "bidirectional"))
    )
    (net (code "60") (name "unconnected-(U2-PD7(ADC10)-Pad27)") (class "Default")
      (node (ref "U2") (pin "27") (pinfunction "PD7(ADC10)_27") (pintype "bidirectional"))
    )
    (net (code "61") (name "unconnected-(U2-UVCC-Pad2)") (class "Default")
      (node (ref "U2") (pin "2") (pinfunction "UVCC_2") (pintype "bidirectional"))
    )
    (net (code "62") (name "unconnected-(U4-INT2-Pad9)") (class "Default")
      (node (ref "U4") (pin "9") (pinfunction "INT2_9") (pintype "output"))
    )
    (net (code "63") (name "unconnected-(U5-SST-Pad4)") (class "Default")
      (node (ref "U5") (pin "4") (pinfunction "SST_4") (pintype "bidirectional"))
    )
  )
)
